# El-Fueradoro_Zuendbox.net
KiCad netlist of a schematic drawn in EAGLE
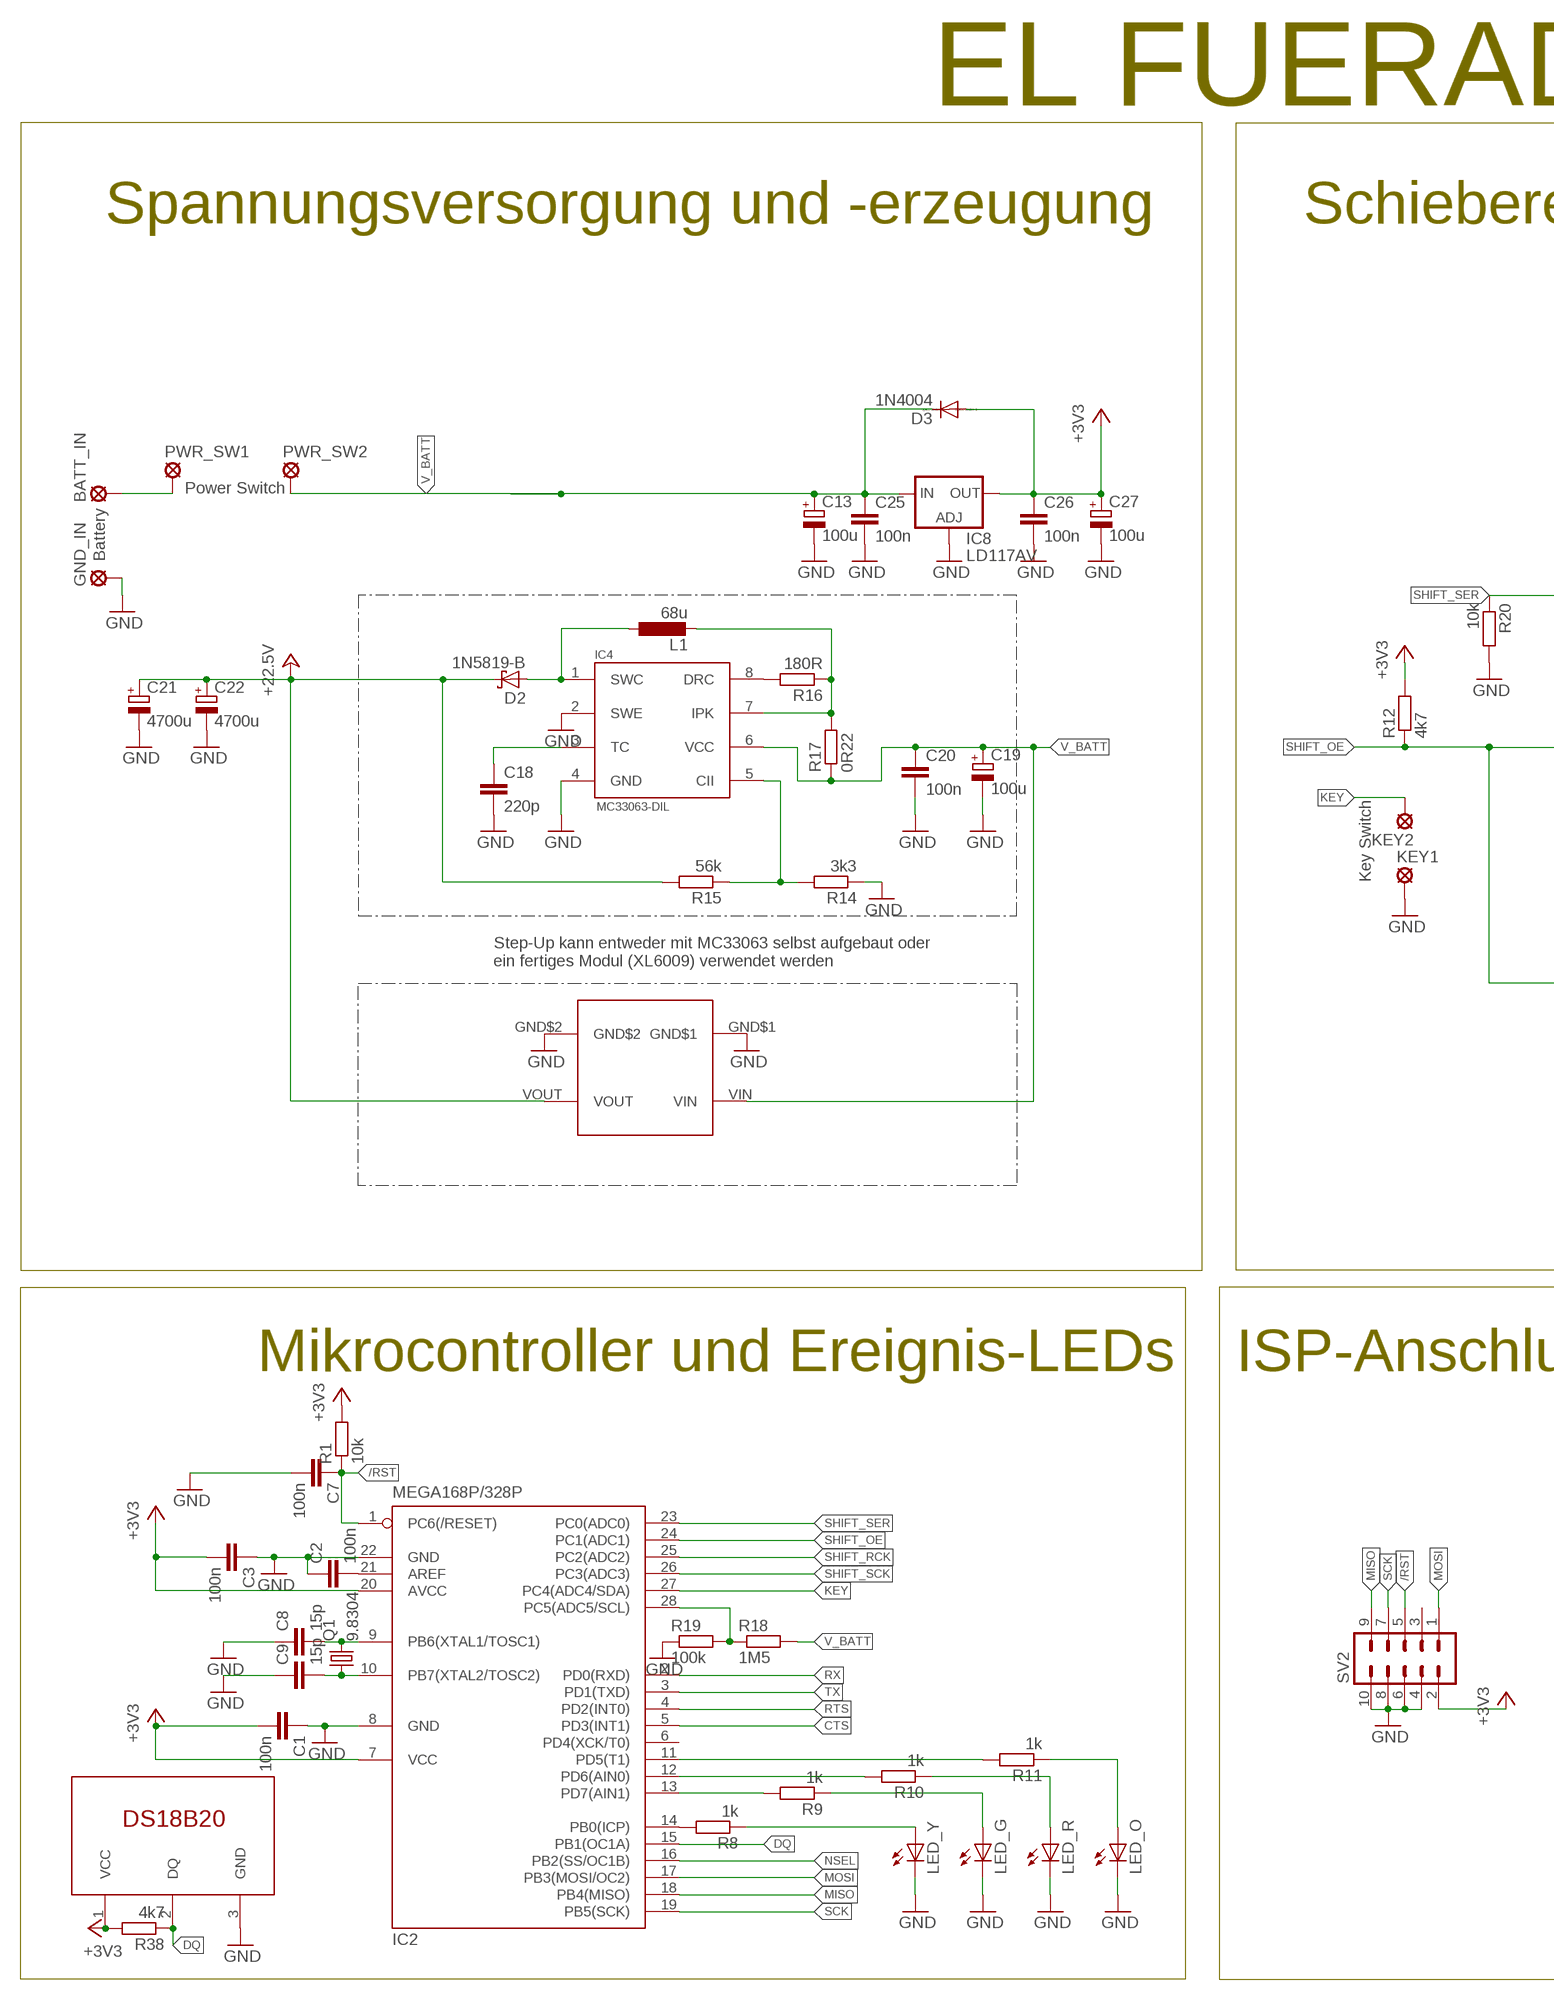
[diagram p0: schematic, sheet 1, part 1 of 2]
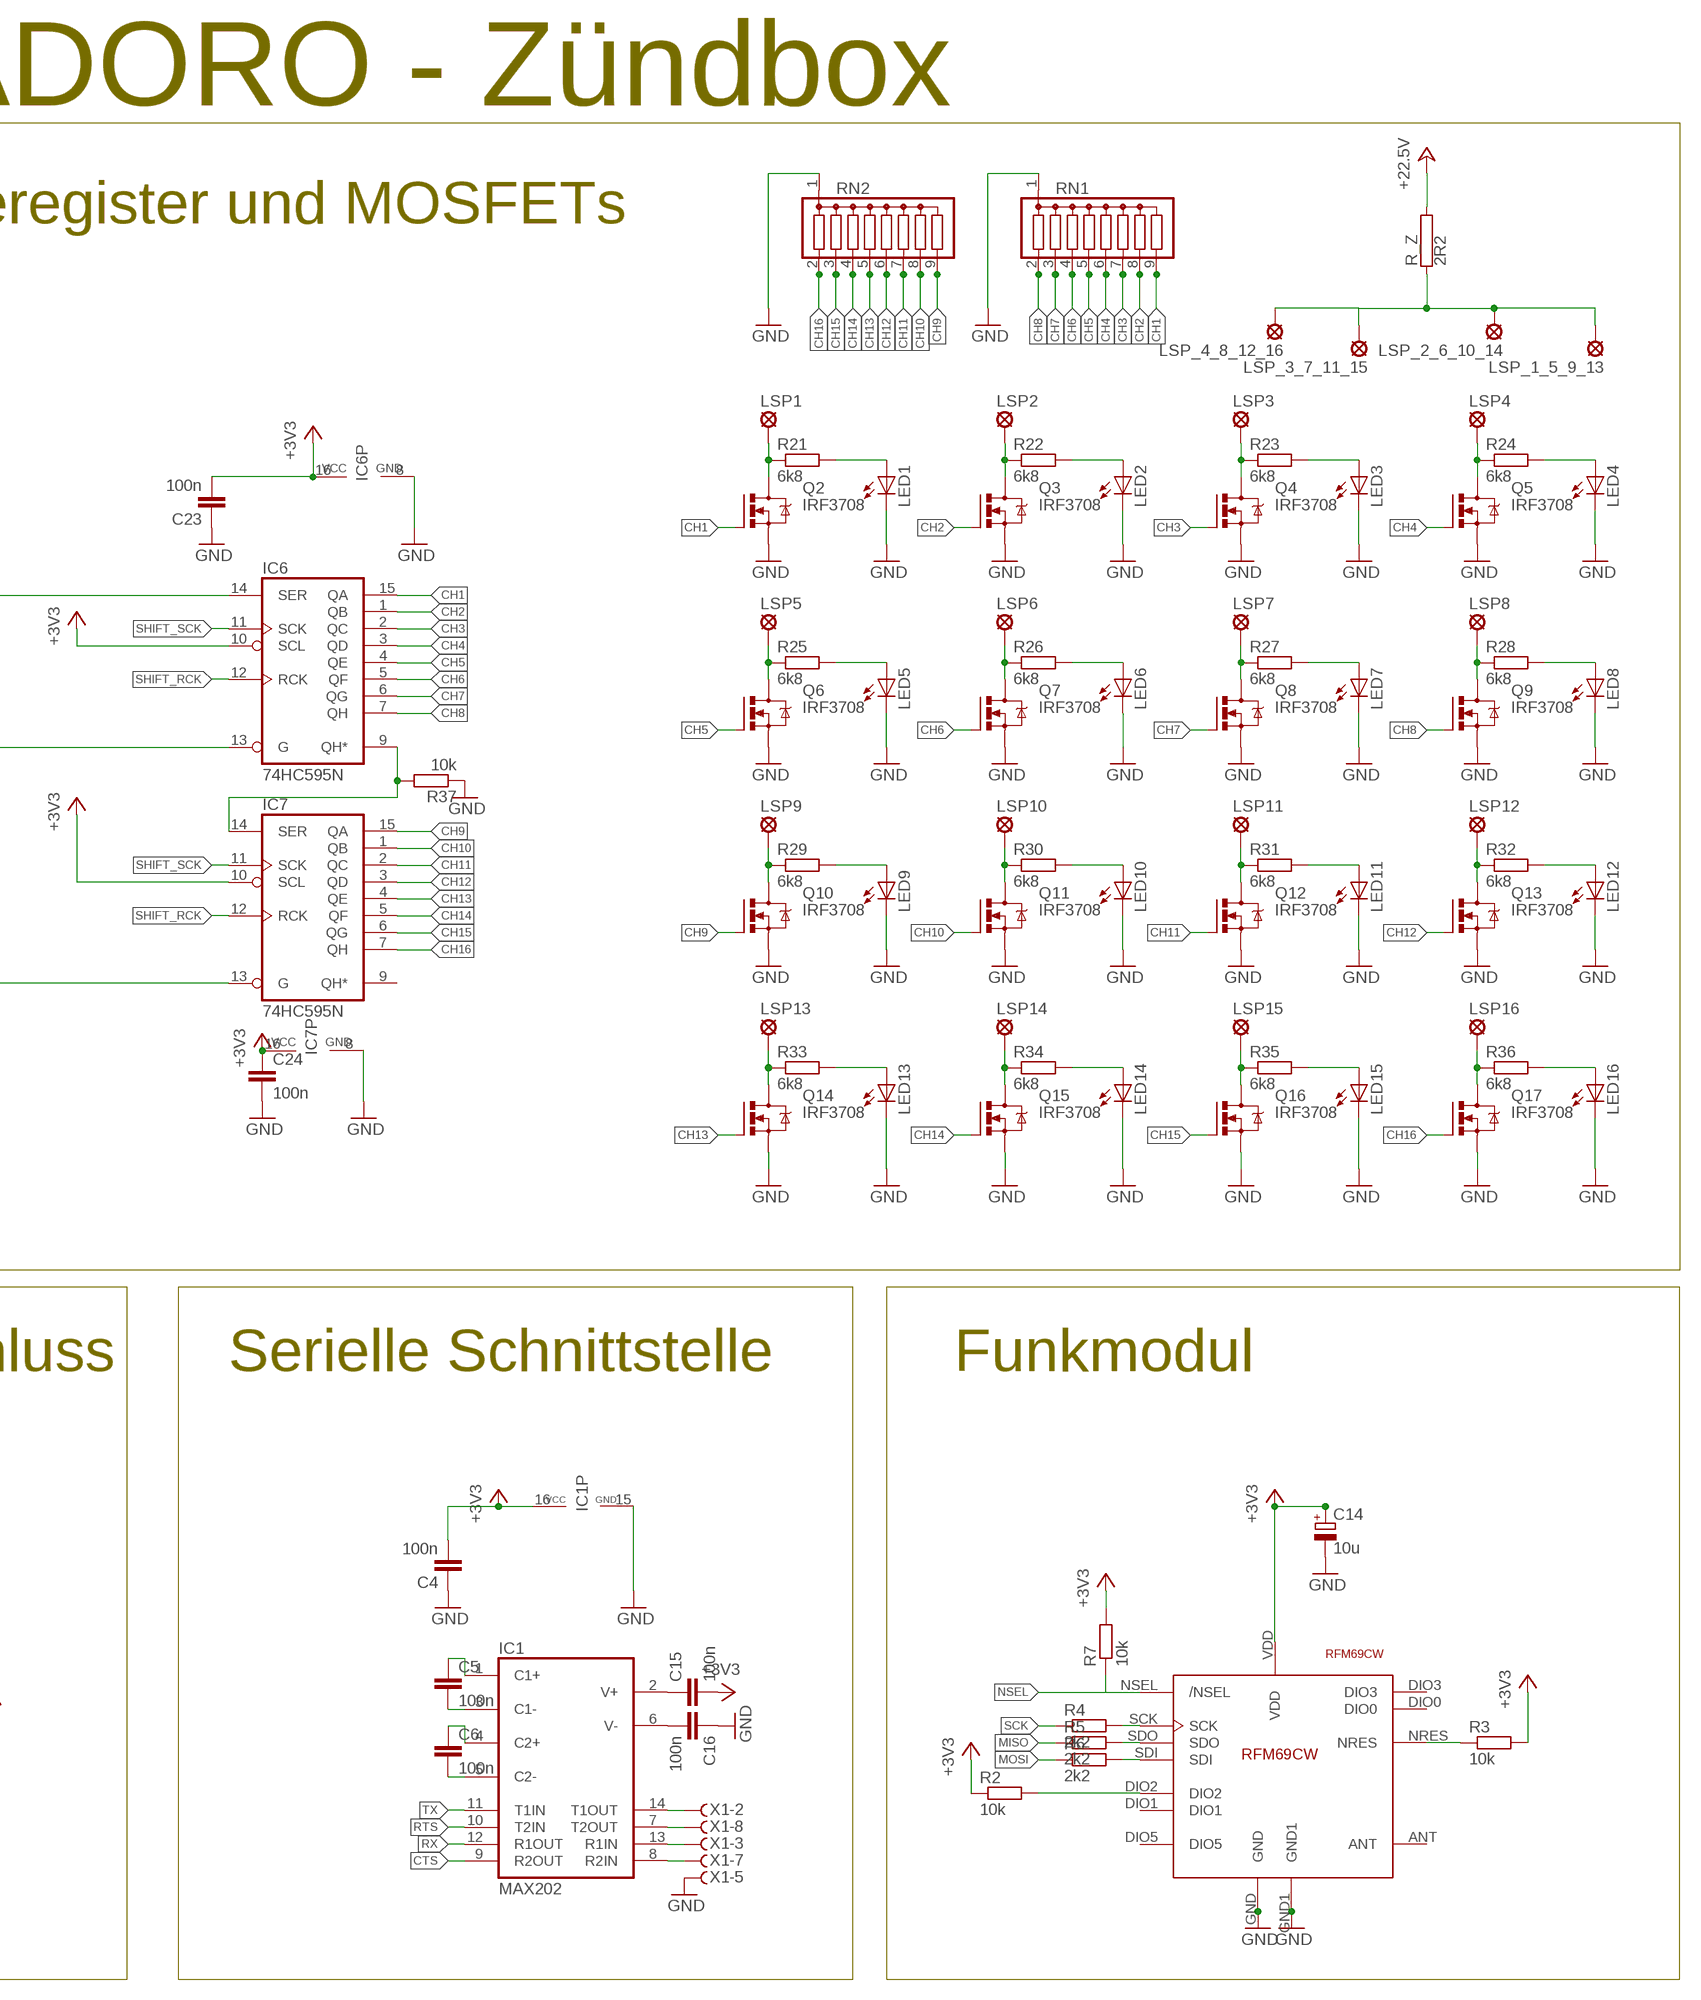
[diagram p1: schematic, sheet 1, part 2 of 2]

(export (version "E")
  (design (tool "Eeschema 10.0.6"))
  (components
    (comp (ref "BATT_IN")
      (value "LSP10")
      (footprint "eagle-import:LSP10")
      (libsource (lib "eagle-import") (part "LSP10"))
    )
    (comp (ref "C1")
      (value "100n")
      (footprint "eagle-import:C025-024X044")
      (libsource (lib "eagle-import") (part "C-EU025-024X044"))
    )
    (comp (ref "C2")
      (value "100n")
      (footprint "eagle-import:C025-024X044")
      (libsource (lib "eagle-import") (part "C-EU025-024X044"))
    )
    (comp (ref "C3")
      (value "100n")
      (footprint "eagle-import:C025-024X044")
      (libsource (lib "eagle-import") (part "C-EU025-024X044"))
    )
    (comp (ref "C4")
      (value "100n")
      (footprint "eagle-import:C025-024X044")
      (libsource (lib "eagle-import") (part "C-EU025-024X044"))
    )
    (comp (ref "C5")
      (value "100n")
      (footprint "eagle-import:C025-024X044")
      (libsource (lib "eagle-import") (part "C-EU025-024X044"))
    )
    (comp (ref "C6")
      (value "100n")
      (footprint "eagle-import:C025-024X044")
      (libsource (lib "eagle-import") (part "C-EU025-024X044"))
    )
    (comp (ref "C7")
      (value "100n")
      (footprint "eagle-import:C025-024X044")
      (libsource (lib "eagle-import") (part "C-EU025-024X044"))
    )
    (comp (ref "C8")
      (value "15p")
      (footprint "eagle-import:C025-024X044")
      (libsource (lib "eagle-import") (part "C-EU025-024X044"))
    )
    (comp (ref "C9")
      (value "15p")
      (footprint "eagle-import:C025-024X044")
      (libsource (lib "eagle-import") (part "C-EU025-024X044"))
    )
    (comp (ref "C13")
      (value "100u")
      (footprint "eagle-import:B45181A")
      (libsource (lib "eagle-import") (part "CPOL-EUB45181A"))
    )
    (comp (ref "C14")
      (value "10u")
      (footprint "eagle-import:B45181A")
      (libsource (lib "eagle-import") (part "CPOL-EUB45181A"))
    )
    (comp (ref "C15")
      (value "100n")
      (footprint "eagle-import:C025-024X044")
      (libsource (lib "eagle-import") (part "C-EU025-024X044"))
    )
    (comp (ref "C16")
      (value "100n")
      (footprint "eagle-import:C025-024X044")
      (libsource (lib "eagle-import") (part "C-EU025-024X044"))
    )
    (comp (ref "C18")
      (value "220p")
      (footprint "eagle-import:C025-024X044")
      (libsource (lib "eagle-import") (part "C-EU025-024X044"))
    )
    (comp (ref "C19")
      (value "100u")
      (footprint "eagle-import:E2,5-6E")
      (libsource (lib "eagle-import") (part "CPOL-EUE2,5-6E"))
    )
    (comp (ref "C20")
      (value "100n")
      (footprint "eagle-import:C025-024X044")
      (libsource (lib "eagle-import") (part "C-EU025-024X044"))
    )
    (comp (ref "C21")
      (value "4700u")
      (footprint "eagle-import:E7,5-18")
      (libsource (lib "eagle-import") (part "CPOL-EUE7.5-18"))
    )
    (comp (ref "C22")
      (value "4700u")
      (footprint "eagle-import:E7,5-18")
      (libsource (lib "eagle-import") (part "CPOL-EUE7.5-18"))
    )
    (comp (ref "C23")
      (value "100n")
      (footprint "eagle-import:C025-024X044")
      (libsource (lib "eagle-import") (part "C-EU025-024X044"))
    )
    (comp (ref "C24")
      (value "100n")
      (footprint "eagle-import:C025-024X044")
      (libsource (lib "eagle-import") (part "C-EU025-024X044"))
    )
    (comp (ref "C25")
      (value "100n")
      (footprint "eagle-import:C025-024X044")
      (libsource (lib "eagle-import") (part "C-EU025-024X044"))
    )
    (comp (ref "C26")
      (value "100n")
      (footprint "eagle-import:C025-024X044")
      (libsource (lib "eagle-import") (part "C-EU025-024X044"))
    )
    (comp (ref "C27")
      (value "100u")
      (footprint "eagle-import:B45181A")
      (libsource (lib "eagle-import") (part "CPOL-EUB45181A"))
    )
    (comp (ref "D2")
      (value "1N5819-B")
      (footprint "eagle-import:DO41-7.6")
      (libsource (lib "eagle-import") (part "1N5819-B"))
    )
    (comp (ref "D3")
      (value "1N4004")
      (footprint "eagle-import:DO41-10")
      (libsource (lib "eagle-import") (part "1N4004"))
    )
    (comp (ref "GND_IN")
      (value "LSP10")
      (footprint "eagle-import:LSP10")
      (libsource (lib "eagle-import") (part "LSP10"))
    )
    (comp (ref "IC1")
      (value "MAX202")
      (footprint "eagle-import:DIL16")
      (fields (field (name "MF") "MAXIM") (field (name "MPN") "MAX232ACPE+"))
      (libsource (lib "eagle-import") (part "MAX232"))
    )
    (comp (ref "IC2")
      (value "MEGA168P/328P")
      (footprint "eagle-import:DIL28-3")
      (libsource (lib "eagle-import") (part "MEGA8-P"))
    )
    (comp (ref "IC4")
      (value "MC33063-DIL")
      (footprint "eagle-import:DIL08")
      (libsource (lib "eagle-import") (part "MC34063-DIL"))
    )
    (comp (ref "IC6")
      (value "74HC595N")
      (footprint "eagle-import:DIL16")
      (libsource (lib "eagle-import") (part "74595NHC"))
    )
    (comp (ref "IC7")
      (value "74HC595N")
      (footprint "eagle-import:DIL16")
      (libsource (lib "eagle-import") (part "74595NHC"))
    )
    (comp (ref "IC8")
      (value "LD117AV")
      (footprint "eagle-import:TO220L1")
      (libsource (lib "eagle-import") (part "LD117A?V"))
    )
    (comp (ref "KEY1")
      (value "LSP10")
      (footprint "eagle-import:LSP10")
      (libsource (lib "eagle-import") (part "LSP10"))
    )
    (comp (ref "KEY2")
      (value "LSP10")
      (footprint "eagle-import:LSP10")
      (libsource (lib "eagle-import") (part "LSP10"))
    )
    (comp (ref "L1")
      (value "68u")
      (footprint "eagle-import:0204_5")
      (libsource (lib "eagle-import") (part "L-EU0204/5"))
    )
    (comp (ref "LED1")
      (value "LED3MM")
      (footprint "eagle-import:LED3MM")
      (libsource (lib "eagle-import") (part "LED3MM"))
    )
    (comp (ref "LED2")
      (value "LED3MM")
      (footprint "eagle-import:LED3MM")
      (libsource (lib "eagle-import") (part "LED3MM"))
    )
    (comp (ref "LED3")
      (value "LED3MM")
      (footprint "eagle-import:LED3MM")
      (libsource (lib "eagle-import") (part "LED3MM"))
    )
    (comp (ref "LED4")
      (value "LED3MM")
      (footprint "eagle-import:LED3MM")
      (libsource (lib "eagle-import") (part "LED3MM"))
    )
    (comp (ref "LED5")
      (value "LED3MM")
      (footprint "eagle-import:LED3MM")
      (libsource (lib "eagle-import") (part "LED3MM"))
    )
    (comp (ref "LED6")
      (value "LED3MM")
      (footprint "eagle-import:LED3MM")
      (libsource (lib "eagle-import") (part "LED3MM"))
    )
    (comp (ref "LED7")
      (value "LED3MM")
      (footprint "eagle-import:LED3MM")
      (libsource (lib "eagle-import") (part "LED3MM"))
    )
    (comp (ref "LED8")
      (value "LED3MM")
      (footprint "eagle-import:LED3MM")
      (libsource (lib "eagle-import") (part "LED3MM"))
    )
    (comp (ref "LED9")
      (value "LED3MM")
      (footprint "eagle-import:LED3MM")
      (libsource (lib "eagle-import") (part "LED3MM"))
    )
    (comp (ref "LED10")
      (value "LED3MM")
      (footprint "eagle-import:LED3MM")
      (libsource (lib "eagle-import") (part "LED3MM"))
    )
    (comp (ref "LED11")
      (value "LED3MM")
      (footprint "eagle-import:LED3MM")
      (libsource (lib "eagle-import") (part "LED3MM"))
    )
    (comp (ref "LED12")
      (value "LED3MM")
      (footprint "eagle-import:LED3MM")
      (libsource (lib "eagle-import") (part "LED3MM"))
    )
    (comp (ref "LED13")
      (value "LED3MM")
      (footprint "eagle-import:LED3MM")
      (libsource (lib "eagle-import") (part "LED3MM"))
    )
    (comp (ref "LED14")
      (value "LED3MM")
      (footprint "eagle-import:LED3MM")
      (libsource (lib "eagle-import") (part "LED3MM"))
    )
    (comp (ref "LED15")
      (value "LED3MM")
      (footprint "eagle-import:LED3MM")
      (libsource (lib "eagle-import") (part "LED3MM"))
    )
    (comp (ref "LED16")
      (value "LED3MM")
      (footprint "eagle-import:LED3MM")
      (libsource (lib "eagle-import") (part "LED3MM"))
    )
    (comp (ref "LED_G")
      (value "LED5MM")
      (footprint "eagle-import:LED5MM")
      (libsource (lib "eagle-import") (part "LED5MM"))
    )
    (comp (ref "LED_O")
      (value "LED5MM")
      (footprint "eagle-import:LED5MM")
      (libsource (lib "eagle-import") (part "LED5MM"))
    )
    (comp (ref "LED_R")
      (value "LED5MM")
      (footprint "eagle-import:LED5MM")
      (libsource (lib "eagle-import") (part "LED5MM"))
    )
    (comp (ref "LED_Y")
      (value "LED5MM")
      (footprint "eagle-import:LED5MM")
      (libsource (lib "eagle-import") (part "LED5MM"))
    )
    (comp (ref "LSP1")
      (value "LSP11")
      (footprint "eagle-import:LSP11")
      (libsource (lib "eagle-import") (part "LSP11"))
    )
    (comp (ref "LSP2")
      (value "LSP11")
      (footprint "eagle-import:LSP11")
      (libsource (lib "eagle-import") (part "LSP11"))
    )
    (comp (ref "LSP3")
      (value "LSP11")
      (footprint "eagle-import:LSP11")
      (libsource (lib "eagle-import") (part "LSP11"))
    )
    (comp (ref "LSP4")
      (value "LSP11")
      (footprint "eagle-import:LSP11")
      (libsource (lib "eagle-import") (part "LSP11"))
    )
    (comp (ref "LSP5")
      (value "LSP11")
      (footprint "eagle-import:LSP11")
      (libsource (lib "eagle-import") (part "LSP11"))
    )
    (comp (ref "LSP6")
      (value "LSP11")
      (footprint "eagle-import:LSP11")
      (libsource (lib "eagle-import") (part "LSP11"))
    )
    (comp (ref "LSP7")
      (value "LSP11")
      (footprint "eagle-import:LSP11")
      (libsource (lib "eagle-import") (part "LSP11"))
    )
    (comp (ref "LSP8")
      (value "LSP11")
      (footprint "eagle-import:LSP11")
      (libsource (lib "eagle-import") (part "LSP11"))
    )
    (comp (ref "LSP9")
      (value "LSP11")
      (footprint "eagle-import:LSP11")
      (libsource (lib "eagle-import") (part "LSP11"))
    )
    (comp (ref "LSP10")
      (value "LSP11")
      (footprint "eagle-import:LSP11")
      (libsource (lib "eagle-import") (part "LSP11"))
    )
    (comp (ref "LSP11")
      (value "LSP11")
      (footprint "eagle-import:LSP11")
      (libsource (lib "eagle-import") (part "LSP11"))
    )
    (comp (ref "LSP12")
      (value "LSP11")
      (footprint "eagle-import:LSP11")
      (libsource (lib "eagle-import") (part "LSP11"))
    )
    (comp (ref "LSP13")
      (value "LSP11")
      (footprint "eagle-import:LSP11")
      (libsource (lib "eagle-import") (part "LSP11"))
    )
    (comp (ref "LSP14")
      (value "LSP11")
      (footprint "eagle-import:LSP11")
      (libsource (lib "eagle-import") (part "LSP11"))
    )
    (comp (ref "LSP15")
      (value "LSP11")
      (footprint "eagle-import:LSP11")
      (libsource (lib "eagle-import") (part "LSP11"))
    )
    (comp (ref "LSP16")
      (value "LSP11")
      (footprint "eagle-import:LSP11")
      (libsource (lib "eagle-import") (part "LSP11"))
    )
    (comp (ref "LSP_1_5_9_13")
      (value "LSP11")
      (footprint "eagle-import:LSP11")
      (libsource (lib "eagle-import") (part "LSP11"))
    )
    (comp (ref "LSP_2_6_10_14")
      (value "LSP11")
      (footprint "eagle-import:LSP11")
      (libsource (lib "eagle-import") (part "LSP11"))
    )
    (comp (ref "LSP_3_7_11_15")
      (value "LSP11")
      (footprint "eagle-import:LSP11")
      (libsource (lib "eagle-import") (part "LSP11"))
    )
    (comp (ref "LSP_4_8_12_16")
      (value "LSP11")
      (footprint "eagle-import:LSP11")
      (libsource (lib "eagle-import") (part "LSP11"))
    )
    (comp (ref "PWR_SW1")
      (value "LSP10")
      (footprint "eagle-import:LSP10")
      (libsource (lib "eagle-import") (part "LSP10"))
    )
    (comp (ref "PWR_SW2")
      (value "LSP10")
      (footprint "eagle-import:LSP10")
      (libsource (lib "eagle-import") (part "LSP10"))
    )
    (comp (ref "Q1")
      (value "9.8304")
      (footprint "eagle-import:HC49_S")
      (libsource (lib "eagle-import") (part "CRYSTALHC49S"))
    )
    (comp (ref "Q2")
      (value "IRF3708")
      (footprint "eagle-import:TO220BV")
      (libsource (lib "eagle-import") (part "IRF530"))
    )
    (comp (ref "Q3")
      (value "IRF3708")
      (footprint "eagle-import:TO220BV")
      (libsource (lib "eagle-import") (part "IRF530"))
    )
    (comp (ref "Q4")
      (value "IRF3708")
      (footprint "eagle-import:TO220BV")
      (libsource (lib "eagle-import") (part "IRF530"))
    )
    (comp (ref "Q5")
      (value "IRF3708")
      (footprint "eagle-import:TO220BV")
      (libsource (lib "eagle-import") (part "IRF530"))
    )
    (comp (ref "Q6")
      (value "IRF3708")
      (footprint "eagle-import:TO220BV")
      (libsource (lib "eagle-import") (part "IRF530"))
    )
    (comp (ref "Q7")
      (value "IRF3708")
      (footprint "eagle-import:TO220BV")
      (libsource (lib "eagle-import") (part "IRF530"))
    )
    (comp (ref "Q8")
      (value "IRF3708")
      (footprint "eagle-import:TO220BV")
      (libsource (lib "eagle-import") (part "IRF530"))
    )
    (comp (ref "Q9")
      (value "IRF3708")
      (footprint "eagle-import:TO220BV")
      (libsource (lib "eagle-import") (part "IRF530"))
    )
    (comp (ref "Q10")
      (value "IRF3708")
      (footprint "eagle-import:TO220BV")
      (libsource (lib "eagle-import") (part "IRF530"))
    )
    (comp (ref "Q11")
      (value "IRF3708")
      (footprint "eagle-import:TO220BV")
      (libsource (lib "eagle-import") (part "IRF530"))
    )
    (comp (ref "Q12")
      (value "IRF3708")
      (footprint "eagle-import:TO220BV")
      (libsource (lib "eagle-import") (part "IRF530"))
    )
    (comp (ref "Q13")
      (value "IRF3708")
      (footprint "eagle-import:TO220BV")
      (libsource (lib "eagle-import") (part "IRF530"))
    )
    (comp (ref "Q14")
      (value "IRF3708")
      (footprint "eagle-import:TO220BV")
      (libsource (lib "eagle-import") (part "IRF530"))
    )
    (comp (ref "Q15")
      (value "IRF3708")
      (footprint "eagle-import:TO220BV")
      (libsource (lib "eagle-import") (part "IRF530"))
    )
    (comp (ref "Q16")
      (value "IRF3708")
      (footprint "eagle-import:TO220BV")
      (libsource (lib "eagle-import") (part "IRF530"))
    )
    (comp (ref "Q17")
      (value "IRF3708")
      (footprint "eagle-import:TO220BV")
      (libsource (lib "eagle-import") (part "IRF530"))
    )
    (comp (ref "R1")
      (value "10k")
      (footprint "eagle-import:0207_10")
      (libsource (lib "eagle-import") (part "R-EU_0207/10"))
    )
    (comp (ref "R2")
      (value "10k")
      (footprint "eagle-import:0207_10")
      (libsource (lib "eagle-import") (part "R-EU_0207/10"))
    )
    (comp (ref "R3")
      (value "10k")
      (footprint "eagle-import:0207_10")
      (libsource (lib "eagle-import") (part "R-EU_0207/10"))
    )
    (comp (ref "R4")
      (value "2k2")
      (footprint "eagle-import:0207_10")
      (libsource (lib "eagle-import") (part "R-EU_0207/10"))
    )
    (comp (ref "R5")
      (value "2k2")
      (footprint "eagle-import:0207_10")
      (libsource (lib "eagle-import") (part "R-EU_0207/10"))
    )
    (comp (ref "R6")
      (value "2k2")
      (footprint "eagle-import:0207_10")
      (libsource (lib "eagle-import") (part "R-EU_0207/10"))
    )
    (comp (ref "R7")
      (value "10k")
      (footprint "eagle-import:0207_10")
      (libsource (lib "eagle-import") (part "R-EU_0207/10"))
    )
    (comp (ref "R8")
      (value "1k")
      (footprint "eagle-import:0207_10")
      (libsource (lib "eagle-import") (part "R-EU_0207/10"))
    )
    (comp (ref "R9")
      (value "1k")
      (footprint "eagle-import:0207_10")
      (libsource (lib "eagle-import") (part "R-EU_0207/10"))
    )
    (comp (ref "R10")
      (value "1k")
      (footprint "eagle-import:0207_10")
      (libsource (lib "eagle-import") (part "R-EU_0207/10"))
    )
    (comp (ref "R11")
      (value "1k")
      (footprint "eagle-import:0207_10")
      (libsource (lib "eagle-import") (part "R-EU_0207/10"))
    )
    (comp (ref "R12")
      (value "4k7")
      (footprint "eagle-import:0207_10")
      (libsource (lib "eagle-import") (part "R-EU_0207/10"))
    )
    (comp (ref "R14")
      (value "3k3")
      (footprint "eagle-import:0207_10")
      (libsource (lib "eagle-import") (part "R-EU_0207/10"))
    )
    (comp (ref "R15")
      (value "56k")
      (footprint "eagle-import:0207_10")
      (libsource (lib "eagle-import") (part "R-EU_0207/10"))
    )
    (comp (ref "R16")
      (value "180R")
      (footprint "eagle-import:0207_10")
      (libsource (lib "eagle-import") (part "R-EU_0207/10"))
    )
    (comp (ref "R17")
      (value "0R22")
      (footprint "eagle-import:0207_10")
      (libsource (lib "eagle-import") (part "R-EU_0207/10"))
    )
    (comp (ref "R18")
      (value "1M5")
      (footprint "eagle-import:0207_10")
      (libsource (lib "eagle-import") (part "R-EU_0207/10"))
    )
    (comp (ref "R19")
      (value "100k")
      (footprint "eagle-import:0207_10")
      (libsource (lib "eagle-import") (part "R-EU_0207/10"))
    )
    (comp (ref "R20")
      (value "10k")
      (footprint "eagle-import:0207_10")
      (libsource (lib "eagle-import") (part "R-EU_0207/10"))
    )
    (comp (ref "R21")
      (value "6k8")
      (footprint "eagle-import:0207_10")
      (libsource (lib "eagle-import") (part "R-EU_0207/10"))
    )
    (comp (ref "R22")
      (value "6k8")
      (footprint "eagle-import:0207_10")
      (libsource (lib "eagle-import") (part "R-EU_0207/10"))
    )
    (comp (ref "R23")
      (value "6k8")
      (footprint "eagle-import:0207_10")
      (libsource (lib "eagle-import") (part "R-EU_0207/10"))
    )
    (comp (ref "R24")
      (value "6k8")
      (footprint "eagle-import:0207_10")
      (libsource (lib "eagle-import") (part "R-EU_0207/10"))
    )
    (comp (ref "R25")
      (value "6k8")
      (footprint "eagle-import:0207_10")
      (libsource (lib "eagle-import") (part "R-EU_0207/10"))
    )
    (comp (ref "R26")
      (value "6k8")
      (footprint "eagle-import:0207_10")
      (libsource (lib "eagle-import") (part "R-EU_0207/10"))
    )
    (comp (ref "R27")
      (value "6k8")
      (footprint "eagle-import:0207_10")
      (libsource (lib "eagle-import") (part "R-EU_0207/10"))
    )
    (comp (ref "R28")
      (value "6k8")
      (footprint "eagle-import:0207_10")
      (libsource (lib "eagle-import") (part "R-EU_0207/10"))
    )
    (comp (ref "R29")
      (value "6k8")
      (footprint "eagle-import:0207_10")
      (libsource (lib "eagle-import") (part "R-EU_0207/10"))
    )
    (comp (ref "R30")
      (value "6k8")
      (footprint "eagle-import:0207_10")
      (libsource (lib "eagle-import") (part "R-EU_0207/10"))
    )
    (comp (ref "R31")
      (value "6k8")
      (footprint "eagle-import:0207_10")
      (libsource (lib "eagle-import") (part "R-EU_0207/10"))
    )
    (comp (ref "R32")
      (value "6k8")
      (footprint "eagle-import:0207_10")
      (libsource (lib "eagle-import") (part "R-EU_0207/10"))
    )
    (comp (ref "R33")
      (value "6k8")
      (footprint "eagle-import:0207_10")
      (libsource (lib "eagle-import") (part "R-EU_0207/10"))
    )
    (comp (ref "R34")
      (value "6k8")
      (footprint "eagle-import:0207_10")
      (libsource (lib "eagle-import") (part "R-EU_0207/10"))
    )
    (comp (ref "R35")
      (value "6k8")
      (footprint "eagle-import:0207_10")
      (libsource (lib "eagle-import") (part "R-EU_0207/10"))
    )
    (comp (ref "R36")
      (value "6k8")
      (footprint "eagle-import:0207_10")
      (libsource (lib "eagle-import") (part "R-EU_0207/10"))
    )
    (comp (ref "R37")
      (value "10k")
      (footprint "eagle-import:0207_10")
      (libsource (lib "eagle-import") (part "R-EU_0207/10"))
    )
    (comp (ref "R38")
      (value "4k7")
      (footprint "eagle-import:0207_10")
      (libsource (lib "eagle-import") (part "R-EU_0207/10"))
    )
    (comp (ref "RN1")
      (value "G08R")
      (footprint "eagle-import:SIL9")
      (libsource (lib "eagle-import") (part "G08R"))
    )
    (comp (ref "RN2")
      (value "G08R")
      (footprint "eagle-import:SIL9")
      (libsource (lib "eagle-import") (part "G08R"))
    )
    (comp (ref "R_Z")
      (value "2R2")
      (footprint "eagle-import:KH214R-8")
      (libsource (lib "eagle-import") (part "RKH214-8R"))
    )
    (comp (ref "SV2")
      (value "ML10")
      (footprint "eagle-import:ML10")
      (libsource (lib "eagle-import") (part "ML10"))
    )
    (comp (ref "U$2")
      (value "DS18B20")
      (footprint "eagle-import:TO92-LINE")
      (libsource (lib "eagle-import") (part "DS18B20"))
    )
    (comp (ref "U$3")
      (value "XL6009_MODULED")
      (footprint "eagle-import:XL6009_PACK")
      (libsource (lib "eagle-import") (part "XL6009_MODULED"))
    )
    (comp (ref "U$4")
      (value "RFM69CW")
      (footprint "eagle-import:RFM69CW")
      (libsource (lib "eagle-import") (part "RFM69CW"))
    )
    (comp (ref "X1")
      (value "F09HPS")
      (footprint "eagle-import:F09HP")
      (libsource (lib "eagle-import") (part "F09HPS"))
    )
  )
  (nets
    (net (code "1") (name "+3V3") (class "Default")
      (node (ref "C1") (pin "2") (pinfunction "2_2") (pintype "passive"))
      (node (ref "C14") (pin "+") (pinfunction "+_+") (pintype "passive"))
      (node (ref "C15") (pin "2") (pinfunction "2_2") (pintype "passive"))
      (node (ref "C23") (pin "2") (pinfunction "2_2") (pintype "passive"))
      (node (ref "C24") (pin "1") (pinfunction "1_1") (pintype "passive"))
      (node (ref "C26") (pin "1") (pinfunction "1_1") (pintype "passive"))
      (node (ref "C27") (pin "+") (pinfunction "+_+") (pintype "passive"))
      (node (ref "C3") (pin "2") (pinfunction "2_2") (pintype "passive"))
      (node (ref "C4") (pin "2") (pinfunction "2_2") (pintype "passive"))
      (node (ref "D3") (pin "A") (pinfunction "A_A") (pintype "passive"))
      (node (ref "IC1") (pin "16") (pinfunction "VCC_16") (pintype "power_in"))
      (node (ref "IC2") (pin "20") (pinfunction "AVCC_20") (pintype "power_in"))
      (node (ref "IC2") (pin "7") (pinfunction "VCC_7") (pintype "power_in"))
      (node (ref "IC6") (pin "10") (pinfunction "SCL_10") (pintype "input"))
      (node (ref "IC6") (pin "16") (pinfunction "VCC_16") (pintype "power_in"))
      (node (ref "IC7") (pin "10") (pinfunction "SCL_10") (pintype "input"))
      (node (ref "IC7") (pin "16") (pinfunction "VCC_16") (pintype "power_in"))
      (node (ref "IC8") (pin "2") (pinfunction "OUT_2") (pintype "passive"))
      (node (ref "R1") (pin "2") (pinfunction "2_2") (pintype "passive"))
      (node (ref "R12") (pin "2") (pinfunction "2_2") (pintype "passive"))
      (node (ref "R2") (pin "1") (pinfunction "1_1") (pintype "passive"))
      (node (ref "R3") (pin "2") (pinfunction "2_2") (pintype "passive"))
      (node (ref "R38") (pin "2") (pinfunction "2_2") (pintype "passive"))
      (node (ref "R7") (pin "2") (pinfunction "2_2") (pintype "passive"))
      (node (ref "SV2") (pin "2") (pinfunction "2_2") (pintype "passive"))
      (node (ref "U$2") (pin "1") (pinfunction "VCC_1") (pintype "power_in"))
      (node (ref "U$4") (pin "VDD") (pinfunction "VDD_VDD") (pintype "power_in"))
    )
    (net (code "2") (name "+22.5V") (class "Default")
      (node (ref "C21") (pin "+") (pinfunction "+_+") (pintype "passive"))
      (node (ref "C22") (pin "+") (pinfunction "+_+") (pintype "passive"))
      (node (ref "D2") (pin "C") (pinfunction "C_C") (pintype "passive"))
      (node (ref "R15") (pin "2") (pinfunction "2_2") (pintype "passive"))
      (node (ref "R_Z") (pin "2") (pinfunction "2_2") (pintype "passive"))
      (node (ref "U$3") (pin "VOUT") (pinfunction "VOUT_VOUT") (pintype "bidirectional"))
    )
    (net (code "3") (name "CH1") (class "Default")
      (node (ref "IC6") (pin "15") (pinfunction "QA_15") (pintype "tri_state"))
      (node (ref "Q2") (pin "G") (pinfunction "G_G") (pintype "passive"))
      (node (ref "RN1") (pin "9") (pinfunction "9_9") (pintype "passive"))
    )
    (net (code "4") (name "CH2") (class "Default")
      (node (ref "IC6") (pin "1") (pinfunction "QB_1") (pintype "tri_state"))
      (node (ref "Q3") (pin "G") (pinfunction "G_G") (pintype "passive"))
      (node (ref "RN1") (pin "8") (pinfunction "8_8") (pintype "passive"))
    )
    (net (code "5") (name "CH3") (class "Default")
      (node (ref "IC6") (pin "2") (pinfunction "QC_2") (pintype "tri_state"))
      (node (ref "Q4") (pin "G") (pinfunction "G_G") (pintype "passive"))
      (node (ref "RN1") (pin "7") (pinfunction "7_7") (pintype "passive"))
    )
    (net (code "6") (name "CH4") (class "Default")
      (node (ref "IC6") (pin "3") (pinfunction "QD_3") (pintype "tri_state"))
      (node (ref "Q5") (pin "G") (pinfunction "G_G") (pintype "passive"))
      (node (ref "RN1") (pin "6") (pinfunction "6_6") (pintype "passive"))
    )
    (net (code "7") (name "CH5") (class "Default")
      (node (ref "IC6") (pin "4") (pinfunction "QE_4") (pintype "tri_state"))
      (node (ref "Q6") (pin "G") (pinfunction "G_G") (pintype "passive"))
      (node (ref "RN1") (pin "5") (pinfunction "5_5") (pintype "passive"))
    )
    (net (code "8") (name "CH6") (class "Default")
      (node (ref "IC6") (pin "5") (pinfunction "QF_5") (pintype "tri_state"))
      (node (ref "Q7") (pin "G") (pinfunction "G_G") (pintype "passive"))
      (node (ref "RN1") (pin "4") (pinfunction "4_4") (pintype "passive"))
    )
    (net (code "9") (name "CH7") (class "Default")
      (node (ref "IC6") (pin "6") (pinfunction "QG_6") (pintype "tri_state"))
      (node (ref "Q8") (pin "G") (pinfunction "G_G") (pintype "passive"))
      (node (ref "RN1") (pin "3") (pinfunction "3_3") (pintype "passive"))
    )
    (net (code "10") (name "CH8") (class "Default")
      (node (ref "IC6") (pin "7") (pinfunction "QH_7") (pintype "tri_state"))
      (node (ref "Q9") (pin "G") (pinfunction "G_G") (pintype "passive"))
      (node (ref "RN1") (pin "2") (pinfunction "2_2") (pintype "passive"))
    )
    (net (code "11") (name "CH9") (class "Default")
      (node (ref "IC7") (pin "15") (pinfunction "QA_15") (pintype "tri_state"))
      (node (ref "Q10") (pin "G") (pinfunction "G_G") (pintype "passive"))
      (node (ref "RN2") (pin "9") (pinfunction "9_9") (pintype "passive"))
    )
    (net (code "12") (name "CH10") (class "Default")
      (node (ref "IC7") (pin "1") (pinfunction "QB_1") (pintype "tri_state"))
      (node (ref "Q11") (pin "G") (pinfunction "G_G") (pintype "passive"))
      (node (ref "RN2") (pin "8") (pinfunction "8_8") (pintype "passive"))
    )
    (net (code "13") (name "CH11") (class "Default")
      (node (ref "IC7") (pin "2") (pinfunction "QC_2") (pintype "tri_state"))
      (node (ref "Q12") (pin "G") (pinfunction "G_G") (pintype "passive"))
      (node (ref "RN2") (pin "7") (pinfunction "7_7") (pintype "passive"))
    )
    (net (code "14") (name "CH12") (class "Default")
      (node (ref "IC7") (pin "3") (pinfunction "QD_3") (pintype "tri_state"))
      (node (ref "Q13") (pin "G") (pinfunction "G_G") (pintype "passive"))
      (node (ref "RN2") (pin "6") (pinfunction "6_6") (pintype "passive"))
    )
    (net (code "15") (name "CH13") (class "Default")
      (node (ref "IC7") (pin "4") (pinfunction "QE_4") (pintype "tri_state"))
      (node (ref "Q14") (pin "G") (pinfunction "G_G") (pintype "passive"))
      (node (ref "RN2") (pin "5") (pinfunction "5_5") (pintype "passive"))
    )
    (net (code "16") (name "CH14") (class "Default")
      (node (ref "IC7") (pin "5") (pinfunction "QF_5") (pintype "tri_state"))
      (node (ref "Q15") (pin "G") (pinfunction "G_G") (pintype "passive"))
      (node (ref "RN2") (pin "4") (pinfunction "4_4") (pintype "passive"))
    )
    (net (code "17") (name "CH15") (class "Default")
      (node (ref "IC7") (pin "6") (pinfunction "QG_6") (pintype "tri_state"))
      (node (ref "Q16") (pin "G") (pinfunction "G_G") (pintype "passive"))
      (node (ref "RN2") (pin "3") (pinfunction "3_3") (pintype "passive"))
    )
    (net (code "18") (name "CH16") (class "Default")
      (node (ref "IC7") (pin "7") (pinfunction "QH_7") (pintype "tri_state"))
      (node (ref "Q17") (pin "G") (pinfunction "G_G") (pintype "passive"))
      (node (ref "RN2") (pin "2") (pinfunction "2_2") (pintype "passive"))
    )
    (net (code "19") (name "CTS") (class "Default")
      (node (ref "IC1") (pin "9") (pinfunction "R2OUT_9") (pintype "output"))
      (node (ref "IC2") (pin "5") (pinfunction "PD3(INT1)_5") (pintype "bidirectional"))
    )
    (net (code "20") (name "DQ") (class "Default")
      (node (ref "IC2") (pin "15") (pinfunction "PB1(OC1A)_15") (pintype "bidirectional"))
      (node (ref "R38") (pin "1") (pinfunction "1_1") (pintype "passive"))
      (node (ref "U$2") (pin "2") (pinfunction "DQ_2") (pintype "bidirectional"))
    )
    (net (code "21") (name "GND") (class "Default")
      (node (ref "C1") (pin "1") (pinfunction "1_1") (pintype "passive"))
      (node (ref "C13") (pin "-") (pinfunction "-_-") (pintype "passive"))
      (node (ref "C14") (pin "-") (pinfunction "-_-") (pintype "passive"))
      (node (ref "C16") (pin "1") (pinfunction "1_1") (pintype "passive"))
      (node (ref "C18") (pin "2") (pinfunction "2_2") (pintype "passive"))
      (node (ref "C19") (pin "-") (pinfunction "-_-") (pintype "passive"))
      (node (ref "C2") (pin "1") (pinfunction "1_1") (pintype "passive"))
      (node (ref "C20") (pin "2") (pinfunction "2_2") (pintype "passive"))
      (node (ref "C21") (pin "-") (pinfunction "-_-") (pintype "passive"))
      (node (ref "C22") (pin "-") (pinfunction "-_-") (pintype "passive"))
      (node (ref "C23") (pin "1") (pinfunction "1_1") (pintype "passive"))
      (node (ref "C24") (pin "2") (pinfunction "2_2") (pintype "passive"))
      (node (ref "C25") (pin "2") (pinfunction "2_2") (pintype "passive"))
      (node (ref "C26") (pin "2") (pinfunction "2_2") (pintype "passive"))
      (node (ref "C27") (pin "-") (pinfunction "-_-") (pintype "passive"))
      (node (ref "C3") (pin "1") (pinfunction "1_1") (pintype "passive"))
      (node (ref "C4") (pin "1") (pinfunction "1_1") (pintype "passive"))
      (node (ref "C7") (pin "2") (pinfunction "2_2") (pintype "passive"))
      (node (ref "C8") (pin "1") (pinfunction "1_1") (pintype "passive"))
      (node (ref "C9") (pin "1") (pinfunction "1_1") (pintype "passive"))
      (node (ref "GND_IN") (pin "MP") (pinfunction "MP_MP") (pintype "passive"))
      (node (ref "IC1") (pin "15") (pinfunction "GND_15") (pintype "power_in"))
      (node (ref "IC2") (pin "22") (pinfunction "GND_22") (pintype "power_in"))
      (node (ref "IC2") (pin "8") (pinfunction "GND_8") (pintype "power_in"))
      (node (ref "IC4") (pin "2") (pinfunction "SWE_2") (pintype "bidirectional"))
      (node (ref "IC4") (pin "4") (pinfunction "GND_4") (pintype "power_in"))
      (node (ref "IC6") (pin "8") (pinfunction "GND_8") (pintype "power_in"))
      (node (ref "IC7") (pin "8") (pinfunction "GND_8") (pintype "power_in"))
      (node (ref "IC8") (pin "1") (pinfunction "ADJ_1") (pintype "input"))
      (node (ref "KEY1") (pin "MP") (pinfunction "MP_MP") (pintype "passive"))
      (node (ref "LED1") (pin "K") (pinfunction "C_K") (pintype "passive"))
      (node (ref "LED10") (pin "K") (pinfunction "C_K") (pintype "passive"))
      (node (ref "LED11") (pin "K") (pinfunction "C_K") (pintype "passive"))
      (node (ref "LED12") (pin "K") (pinfunction "C_K") (pintype "passive"))
      (node (ref "LED13") (pin "K") (pinfunction "C_K") (pintype "passive"))
      (node (ref "LED14") (pin "K") (pinfunction "C_K") (pintype "passive"))
      (node (ref "LED15") (pin "K") (pinfunction "C_K") (pintype "passive"))
      (node (ref "LED16") (pin "K") (pinfunction "C_K") (pintype "passive"))
      (node (ref "LED2") (pin "K") (pinfunction "C_K") (pintype "passive"))
      (node (ref "LED3") (pin "K") (pinfunction "C_K") (pintype "passive"))
      (node (ref "LED4") (pin "K") (pinfunction "C_K") (pintype "passive"))
      (node (ref "LED5") (pin "K") (pinfunction "C_K") (pintype "passive"))
      (node (ref "LED6") (pin "K") (pinfunction "C_K") (pintype "passive"))
      (node (ref "LED7") (pin "K") (pinfunction "C_K") (pintype "passive"))
      (node (ref "LED8") (pin "K") (pinfunction "C_K") (pintype "passive"))
      (node (ref "LED9") (pin "K") (pinfunction "C_K") (pintype "passive"))
      (node (ref "LED_G") (pin "K") (pinfunction "C_K") (pintype "passive"))
      (node (ref "LED_O") (pin "K") (pinfunction "C_K") (pintype "passive"))
      (node (ref "LED_R") (pin "K") (pinfunction "C_K") (pintype "passive"))
      (node (ref "LED_Y") (pin "K") (pinfunction "C_K") (pintype "passive"))
      (node (ref "Q10") (pin "S") (pinfunction "S_S") (pintype "passive"))
      (node (ref "Q11") (pin "S") (pinfunction "S_S") (pintype "passive"))
      (node (ref "Q12") (pin "S") (pinfunction "S_S") (pintype "passive"))
      (node (ref "Q13") (pin "S") (pinfunction "S_S") (pintype "passive"))
      (node (ref "Q14") (pin "S") (pinfunction "S_S") (pintype "passive"))
      (node (ref "Q15") (pin "S") (pinfunction "S_S") (pintype "passive"))
      (node (ref "Q16") (pin "S") (pinfunction "S_S") (pintype "passive"))
      (node (ref "Q17") (pin "S") (pinfunction "S_S") (pintype "passive"))
      (node (ref "Q2") (pin "S") (pinfunction "S_S") (pintype "passive"))
      (node (ref "Q3") (pin "S") (pinfunction "S_S") (pintype "passive"))
      (node (ref "Q4") (pin "S") (pinfunction "S_S") (pintype "passive"))
      (node (ref "Q5") (pin "S") (pinfunction "S_S") (pintype "passive"))
      (node (ref "Q6") (pin "S") (pinfunction "S_S") (pintype "passive"))
      (node (ref "Q7") (pin "S") (pinfunction "S_S") (pintype "passive"))
      (node (ref "Q8") (pin "S") (pinfunction "S_S") (pintype "passive"))
      (node (ref "Q9") (pin "S") (pinfunction "S_S") (pintype "passive"))
      (node (ref "R14") (pin "1") (pinfunction "1_1") (pintype "passive"))
      (node (ref "R19") (pin "1") (pinfunction "1_1") (pintype "passive"))
      (node (ref "R20") (pin "2") (pinfunction "2_2") (pintype "passive"))
      (node (ref "R37") (pin "1") (pinfunction "1_1") (pintype "passive"))
      (node (ref "RN1") (pin "1") (pinfunction "1_1") (pintype "passive"))
      (node (ref "RN2") (pin "1") (pinfunction "1_1") (pintype "passive"))
      (node (ref "SV2") (pin "10") (pinfunction "10_10") (pintype "passive"))
      (node (ref "SV2") (pin "4") (pinfunction "4_4") (pintype "passive"))
      (node (ref "SV2") (pin "6") (pinfunction "6_6") (pintype "passive"))
      (node (ref "SV2") (pin "8") (pinfunction "8_8") (pintype "passive"))
      (node (ref "U$2") (pin "3") (pinfunction "GND_3") (pintype "power_in"))
      (node (ref "U$3") (pin "GND$1") (pinfunction "GND$1_GND$1") (pintype "bidirectional"))
      (node (ref "U$3") (pin "GND$2") (pinfunction "GND$2_GND$2") (pintype "bidirectional"))
      (node (ref "U$4") (pin "GND") (pinfunction "GND_GND") (pintype "power_in"))
      (node (ref "U$4") (pin "GND1") (pinfunction "GND1_GND1") (pintype "power_in"))
      (node (ref "X1") (pin "5") (pinfunction "F_5") (pintype "passive"))
    )
    (net (code "22") (name "KEY") (class "Default")
      (node (ref "IC2") (pin "27") (pinfunction "PC4(ADC4/SDA)_27") (pintype "bidirectional"))
      (node (ref "KEY2") (pin "MP") (pinfunction "MP_MP") (pintype "passive"))
    )
    (net (code "23") (name "MISO") (class "Default")
      (node (ref "IC2") (pin "18") (pinfunction "PB4(MISO)_18") (pintype "bidirectional"))
      (node (ref "R5") (pin "1") (pinfunction "1_1") (pintype "passive"))
      (node (ref "SV2") (pin "9") (pinfunction "9_9") (pintype "passive"))
    )
    (net (code "24") (name "MOSI") (class "Default")
      (node (ref "IC2") (pin "17") (pinfunction "PB3(MOSI/OC2)_17") (pintype "bidirectional"))
      (node (ref "R6") (pin "1") (pinfunction "1_1") (pintype "passive"))
      (node (ref "SV2") (pin "1") (pinfunction "1_1") (pintype "passive"))
    )
    (net (code "25") (name "NSEL") (class "Default")
      (node (ref "IC2") (pin "16") (pinfunction "PB2(SS/OC1B)_16") (pintype "bidirectional"))
      (node (ref "R7") (pin "1") (pinfunction "1_1") (pintype "passive"))
      (node (ref "U$4") (pin "NSEL") (pinfunction "/NSEL_NSEL") (pintype "input"))
    )
    (net (code "26") (name "Net-(BATT_IN-PadMP)") (class "Default")
      (node (ref "BATT_IN") (pin "MP") (pinfunction "MP_MP") (pintype "passive"))
      (node (ref "PWR_SW1") (pin "MP") (pinfunction "MP_MP") (pintype "passive"))
    )
    (net (code "27") (name "Net-(IC1A-C1+)") (class "Default")
      (node (ref "C5") (pin "1") (pinfunction "1_1") (pintype "passive"))
      (node (ref "IC1") (pin "1") (pinfunction "C1+_1") (pintype "bidirectional"))
    )
    (net (code "28") (name "Net-(IC1A-C1-)") (class "Default")
      (node (ref "C5") (pin "2") (pinfunction "2_2") (pintype "passive"))
      (node (ref "IC1") (pin "3") (pinfunction "C1-_3") (pintype "bidirectional"))
    )
    (net (code "29") (name "Net-(IC1A-C2+)") (class "Default")
      (node (ref "C6") (pin "1") (pinfunction "1_1") (pintype "passive"))
      (node (ref "IC1") (pin "4") (pinfunction "C2+_4") (pintype "bidirectional"))
    )
    (net (code "30") (name "Net-(IC1A-C2-)") (class "Default")
      (node (ref "C6") (pin "2") (pinfunction "2_2") (pintype "passive"))
      (node (ref "IC1") (pin "5") (pinfunction "C2-_5") (pintype "bidirectional"))
    )
    (net (code "31") (name "Net-(IC1A-R1IN)") (class "Default")
      (node (ref "IC1") (pin "13") (pinfunction "R1IN_13") (pintype "input"))
      (node (ref "X1") (pin "3") (pinfunction "F_3") (pintype "passive"))
    )
    (net (code "32") (name "Net-(IC1A-R2IN)") (class "Default")
      (node (ref "IC1") (pin "8") (pinfunction "R2IN_8") (pintype "input"))
      (node (ref "X1") (pin "7") (pinfunction "F_7") (pintype "passive"))
    )
    (net (code "33") (name "Net-(IC1A-T1OUT)") (class "Default")
      (node (ref "IC1") (pin "14") (pinfunction "T1OUT_14") (pintype "output"))
      (node (ref "X1") (pin "2") (pinfunction "F_2") (pintype "passive"))
    )
    (net (code "34") (name "Net-(IC1A-T2OUT)") (class "Default")
      (node (ref "IC1") (pin "7") (pinfunction "T2OUT_7") (pintype "output"))
      (node (ref "X1") (pin "8") (pinfunction "F_8") (pintype "passive"))
    )
    (net (code "35") (name "Net-(IC1A-V+)") (class "Default")
      (node (ref "C15") (pin "1") (pinfunction "1_1") (pintype "passive"))
      (node (ref "IC1") (pin "2") (pinfunction "V+_2") (pintype "bidirectional"))
    )
    (net (code "36") (name "Net-(IC1A-V-)") (class "Default")
      (node (ref "C16") (pin "2") (pinfunction "2_2") (pintype "passive"))
      (node (ref "IC1") (pin "6") (pinfunction "V-_6") (pintype "bidirectional"))
    )
    (net (code "37") (name "Net-(IC2-AREF)") (class "Default")
      (node (ref "C2") (pin "2") (pinfunction "2_2") (pintype "passive"))
      (node (ref "IC2") (pin "21") (pinfunction "AREF_21") (pintype "passive"))
    )
    (net (code "38") (name "Net-(IC2-PB0(ICP))") (class "Default")
      (node (ref "IC2") (pin "14") (pinfunction "PB0(ICP)_14") (pintype "bidirectional"))
      (node (ref "R8") (pin "2") (pinfunction "2_2") (pintype "passive"))
    )
    (net (code "39") (name "Net-(IC2-PB6(XTAL1{slash}TOSC1))") (class "Default")
      (node (ref "C8") (pin "2") (pinfunction "2_2") (pintype "passive"))
      (node (ref "IC2") (pin "9") (pinfunction "PB6(XTAL1/TOSC1)_9") (pintype "bidirectional"))
      (node (ref "Q1") (pin "2") (pinfunction "2_2") (pintype "passive"))
    )
    (net (code "40") (name "Net-(IC2-PB7(XTAL2{slash}TOSC2))") (class "Default")
      (node (ref "C9") (pin "2") (pinfunction "2_2") (pintype "passive"))
      (node (ref "IC2") (pin "10") (pinfunction "PB7(XTAL2/TOSC2)_10") (pintype "bidirectional"))
      (node (ref "Q1") (pin "1") (pinfunction "1_1") (pintype "passive"))
    )
    (net (code "41") (name "Net-(IC2-PC5(ADC5{slash}SCL))") (class "Default")
      (node (ref "IC2") (pin "28") (pinfunction "PC5(ADC5/SCL)_28") (pintype "bidirectional"))
      (node (ref "R18") (pin "1") (pinfunction "1_1") (pintype "passive"))
      (node (ref "R19") (pin "2") (pinfunction "2_2") (pintype "passive"))
    )
    (net (code "42") (name "Net-(IC2-PD5(T1))") (class "Default")
      (node (ref "IC2") (pin "11") (pinfunction "PD5(T1)_11") (pintype "bidirectional"))
      (node (ref "R11") (pin "2") (pinfunction "2_2") (pintype "passive"))
    )
    (net (code "43") (name "Net-(IC2-PD6(AIN0))") (class "Default")
      (node (ref "IC2") (pin "12") (pinfunction "PD6(AIN0)_12") (pintype "bidirectional"))
      (node (ref "R10") (pin "2") (pinfunction "2_2") (pintype "passive"))
    )
    (net (code "44") (name "Net-(IC2-PD7(AIN1))") (class "Default")
      (node (ref "IC2") (pin "13") (pinfunction "PD7(AIN1)_13") (pintype "bidirectional"))
      (node (ref "R9") (pin "2") (pinfunction "2_2") (pintype "passive"))
    )
    (net (code "45") (name "Net-(IC4-CII)") (class "Default")
      (node (ref "IC4") (pin "5") (pinfunction "CII_5") (pintype "bidirectional"))
      (node (ref "R14") (pin "2") (pinfunction "2_2") (pintype "passive"))
      (node (ref "R15") (pin "1") (pinfunction "1_1") (pintype "passive"))
    )
    (net (code "46") (name "Net-(IC4-DRC)") (class "Default")
      (node (ref "IC4") (pin "8") (pinfunction "DRC_8") (pintype "bidirectional"))
      (node (ref "R16") (pin "2") (pinfunction "2_2") (pintype "passive"))
    )
    (net (code "47") (name "Net-(IC4-IPK)") (class "Default")
      (node (ref "IC4") (pin "7") (pinfunction "IPK_7") (pintype "bidirectional"))
      (node (ref "L1") (pin "2") (pinfunction "2_2") (pintype "passive"))
      (node (ref "R16") (pin "1") (pinfunction "1_1") (pintype "passive"))
      (node (ref "R17") (pin "2") (pinfunction "2_2") (pintype "passive"))
    )
    (net (code "48") (name "Net-(IC4-SWC)") (class "Default")
      (node (ref "D2") (pin "A") (pinfunction "A_A") (pintype "passive"))
      (node (ref "IC4") (pin "1") (pinfunction "SWC_1") (pintype "bidirectional"))
      (node (ref "L1") (pin "1") (pinfunction "1_1") (pintype "passive"))
    )
    (net (code "49") (name "Net-(IC4-TC)") (class "Default")
      (node (ref "C18") (pin "1") (pinfunction "1_1") (pintype "passive"))
      (node (ref "IC4") (pin "3") (pinfunction "TC_3") (pintype "bidirectional"))
    )
    (net (code "50") (name "Net-(IC6A-QH*)") (class "Default")
      (node (ref "IC6") (pin "9") (pinfunction "QH*_9") (pintype "tri_state"))
      (node (ref "IC7") (pin "14") (pinfunction "SER_14") (pintype "input"))
      (node (ref "R37") (pin "2") (pinfunction "2_2") (pintype "passive"))
    )
    (net (code "51") (name "Net-(LED1-PadA)") (class "Default")
      (node (ref "LED1") (pin "A") (pinfunction "A_A") (pintype "passive"))
      (node (ref "R21") (pin "2") (pinfunction "2_2") (pintype "passive"))
    )
    (net (code "52") (name "Net-(LED2-PadA)") (class "Default")
      (node (ref "LED2") (pin "A") (pinfunction "A_A") (pintype "passive"))
      (node (ref "R22") (pin "2") (pinfunction "2_2") (pintype "passive"))
    )
    (net (code "53") (name "Net-(LED3-PadA)") (class "Default")
      (node (ref "LED3") (pin "A") (pinfunction "A_A") (pintype "passive"))
      (node (ref "R23") (pin "2") (pinfunction "2_2") (pintype "passive"))
    )
    (net (code "54") (name "Net-(LED4-PadA)") (class "Default")
      (node (ref "LED4") (pin "A") (pinfunction "A_A") (pintype "passive"))
      (node (ref "R24") (pin "2") (pinfunction "2_2") (pintype "passive"))
    )
    (net (code "55") (name "Net-(LED5-PadA)") (class "Default")
      (node (ref "LED5") (pin "A") (pinfunction "A_A") (pintype "passive"))
      (node (ref "R25") (pin "2") (pinfunction "2_2") (pintype "passive"))
    )
    (net (code "56") (name "Net-(LED6-PadA)") (class "Default")
      (node (ref "LED6") (pin "A") (pinfunction "A_A") (pintype "passive"))
      (node (ref "R26") (pin "2") (pinfunction "2_2") (pintype "passive"))
    )
    (net (code "57") (name "Net-(LED7-PadA)") (class "Default")
      (node (ref "LED7") (pin "A") (pinfunction "A_A") (pintype "passive"))
      (node (ref "R27") (pin "2") (pinfunction "2_2") (pintype "passive"))
    )
    (net (code "58") (name "Net-(LED8-PadA)") (class "Default")
      (node (ref "LED8") (pin "A") (pinfunction "A_A") (pintype "passive"))
      (node (ref "R28") (pin "2") (pinfunction "2_2") (pintype "passive"))
    )
    (net (code "59") (name "Net-(LED9-PadA)") (class "Default")
      (node (ref "LED9") (pin "A") (pinfunction "A_A") (pintype "passive"))
      (node (ref "R29") (pin "2") (pinfunction "2_2") (pintype "passive"))
    )
    (net (code "60") (name "Net-(LED10-PadA)") (class "Default")
      (node (ref "LED10") (pin "A") (pinfunction "A_A") (pintype "passive"))
      (node (ref "R30") (pin "2") (pinfunction "2_2") (pintype "passive"))
    )
    (net (code "61") (name "Net-(LED11-PadA)") (class "Default")
      (node (ref "LED11") (pin "A") (pinfunction "A_A") (pintype "passive"))
      (node (ref "R31") (pin "2") (pinfunction "2_2") (pintype "passive"))
    )
    (net (code "62") (name "Net-(LED12-PadA)") (class "Default")
      (node (ref "LED12") (pin "A") (pinfunction "A_A") (pintype "passive"))
      (node (ref "R32") (pin "2") (pinfunction "2_2") (pintype "passive"))
    )
    (net (code "63") (name "Net-(LED13-PadA)") (class "Default")
      (node (ref "LED13") (pin "A") (pinfunction "A_A") (pintype "passive"))
      (node (ref "R33") (pin "2") (pinfunction "2_2") (pintype "passive"))
    )
    (net (code "64") (name "Net-(LED14-PadA)") (class "Default")
      (node (ref "LED14") (pin "A") (pinfunction "A_A") (pintype "passive"))
      (node (ref "R34") (pin "2") (pinfunction "2_2") (pintype "passive"))
    )
    (net (code "65") (name "Net-(LED15-PadA)") (class "Default")
      (node (ref "LED15") (pin "A") (pinfunction "A_A") (pintype "passive"))
      (node (ref "R35") (pin "2") (pinfunction "2_2") (pintype "passive"))
    )
    (net (code "66") (name "Net-(LED16-PadA)") (class "Default")
      (node (ref "LED16") (pin "A") (pinfunction "A_A") (pintype "passive"))
      (node (ref "R36") (pin "2") (pinfunction "2_2") (pintype "passive"))
    )
    (net (code "67") (name "Net-(LED_G-PadA)") (class "Default")
      (node (ref "LED_G") (pin "A") (pinfunction "A_A") (pintype "passive"))
      (node (ref "R9") (pin "1") (pinfunction "1_1") (pintype "passive"))
    )
    (net (code "68") (name "Net-(LED_O-PadA)") (class "Default")
      (node (ref "LED_O") (pin "A") (pinfunction "A_A") (pintype "passive"))
      (node (ref "R11") (pin "1") (pinfunction "1_1") (pintype "passive"))
    )
    (net (code "69") (name "Net-(LED_R-PadA)") (class "Default")
      (node (ref "LED_R") (pin "A") (pinfunction "A_A") (pintype "passive"))
      (node (ref "R10") (pin "1") (pinfunction "1_1") (pintype "passive"))
    )
    (net (code "70") (name "Net-(LED_Y-PadA)") (class "Default")
      (node (ref "LED_Y") (pin "A") (pinfunction "A_A") (pintype "passive"))
      (node (ref "R8") (pin "1") (pinfunction "1_1") (pintype "passive"))
    )
    (net (code "71") (name "Net-(LSP1-PadMP)") (class "Default")
      (node (ref "LSP1") (pin "MP") (pinfunction "MP_MP") (pintype "passive"))
      (node (ref "Q2") (pin "D") (pinfunction "D_D") (pintype "passive"))
      (node (ref "R21") (pin "1") (pinfunction "1_1") (pintype "passive"))
    )
    (net (code "72") (name "Net-(LSP2-PadMP)") (class "Default")
      (node (ref "LSP2") (pin "MP") (pinfunction "MP_MP") (pintype "passive"))
      (node (ref "Q3") (pin "D") (pinfunction "D_D") (pintype "passive"))
      (node (ref "R22") (pin "1") (pinfunction "1_1") (pintype "passive"))
    )
    (net (code "73") (name "Net-(LSP3-PadMP)") (class "Default")
      (node (ref "LSP3") (pin "MP") (pinfunction "MP_MP") (pintype "passive"))
      (node (ref "Q4") (pin "D") (pinfunction "D_D") (pintype "passive"))
      (node (ref "R23") (pin "1") (pinfunction "1_1") (pintype "passive"))
    )
    (net (code "74") (name "Net-(LSP4-PadMP)") (class "Default")
      (node (ref "LSP4") (pin "MP") (pinfunction "MP_MP") (pintype "passive"))
      (node (ref "Q5") (pin "D") (pinfunction "D_D") (pintype "passive"))
      (node (ref "R24") (pin "1") (pinfunction "1_1") (pintype "passive"))
    )
    (net (code "75") (name "Net-(LSP5-PadMP)") (class "Default")
      (node (ref "LSP5") (pin "MP") (pinfunction "MP_MP") (pintype "passive"))
      (node (ref "Q6") (pin "D") (pinfunction "D_D") (pintype "passive"))
      (node (ref "R25") (pin "1") (pinfunction "1_1") (pintype "passive"))
    )
    (net (code "76") (name "Net-(LSP6-PadMP)") (class "Default")
      (node (ref "LSP6") (pin "MP") (pinfunction "MP_MP") (pintype "passive"))
      (node (ref "Q7") (pin "D") (pinfunction "D_D") (pintype "passive"))
      (node (ref "R26") (pin "1") (pinfunction "1_1") (pintype "passive"))
    )
    (net (code "77") (name "Net-(LSP7-PadMP)") (class "Default")
      (node (ref "LSP7") (pin "MP") (pinfunction "MP_MP") (pintype "passive"))
      (node (ref "Q8") (pin "D") (pinfunction "D_D") (pintype "passive"))
      (node (ref "R27") (pin "1") (pinfunction "1_1") (pintype "passive"))
    )
    (net (code "78") (name "Net-(LSP8-PadMP)") (class "Default")
      (node (ref "LSP8") (pin "MP") (pinfunction "MP_MP") (pintype "passive"))
      (node (ref "Q9") (pin "D") (pinfunction "D_D") (pintype "passive"))
      (node (ref "R28") (pin "1") (pinfunction "1_1") (pintype "passive"))
    )
    (net (code "79") (name "Net-(LSP9-PadMP)") (class "Default")
      (node (ref "LSP9") (pin "MP") (pinfunction "MP_MP") (pintype "passive"))
      (node (ref "Q10") (pin "D") (pinfunction "D_D") (pintype "passive"))
      (node (ref "R29") (pin "1") (pinfunction "1_1") (pintype "passive"))
    )
    (net (code "80") (name "Net-(LSP10-PadMP)") (class "Default")
      (node (ref "LSP10") (pin "MP") (pinfunction "MP_MP") (pintype "passive"))
      (node (ref "Q11") (pin "D") (pinfunction "D_D") (pintype "passive"))
      (node (ref "R30") (pin "1") (pinfunction "1_1") (pintype "passive"))
    )
    (net (code "81") (name "Net-(LSP11-PadMP)") (class "Default")
      (node (ref "LSP11") (pin "MP") (pinfunction "MP_MP") (pintype "passive"))
      (node (ref "Q12") (pin "D") (pinfunction "D_D") (pintype "passive"))
      (node (ref "R31") (pin "1") (pinfunction "1_1") (pintype "passive"))
    )
    (net (code "82") (name "Net-(LSP12-PadMP)") (class "Default")
      (node (ref "LSP12") (pin "MP") (pinfunction "MP_MP") (pintype "passive"))
      (node (ref "Q13") (pin "D") (pinfunction "D_D") (pintype "passive"))
      (node (ref "R32") (pin "1") (pinfunction "1_1") (pintype "passive"))
    )
    (net (code "83") (name "Net-(LSP13-PadMP)") (class "Default")
      (node (ref "LSP13") (pin "MP") (pinfunction "MP_MP") (pintype "passive"))
      (node (ref "Q14") (pin "D") (pinfunction "D_D") (pintype "passive"))
      (node (ref "R33") (pin "1") (pinfunction "1_1") (pintype "passive"))
    )
    (net (code "84") (name "Net-(LSP14-PadMP)") (class "Default")
      (node (ref "LSP14") (pin "MP") (pinfunction "MP_MP") (pintype "passive"))
      (node (ref "Q15") (pin "D") (pinfunction "D_D") (pintype "passive"))
      (node (ref "R34") (pin "1") (pinfunction "1_1") (pintype "passive"))
    )
    (net (code "85") (name "Net-(LSP15-PadMP)") (class "Default")
      (node (ref "LSP15") (pin "MP") (pinfunction "MP_MP") (pintype "passive"))
      (node (ref "Q16") (pin "D") (pinfunction "D_D") (pintype "passive"))
      (node (ref "R35") (pin "1") (pinfunction "1_1") (pintype "passive"))
    )
    (net (code "86") (name "Net-(LSP16-PadMP)") (class "Default")
      (node (ref "LSP16") (pin "MP") (pinfunction "MP_MP") (pintype "passive"))
      (node (ref "Q17") (pin "D") (pinfunction "D_D") (pintype "passive"))
      (node (ref "R36") (pin "1") (pinfunction "1_1") (pintype "passive"))
    )
    (net (code "87") (name "Net-(LSP_1_5_9_13-PadMP)") (class "Default")
      (node (ref "LSP_1_5_9_13") (pin "MP") (pinfunction "MP_MP") (pintype "passive"))
      (node (ref "LSP_2_6_10_14") (pin "MP") (pinfunction "MP_MP") (pintype "passive"))
      (node (ref "LSP_3_7_11_15") (pin "MP") (pinfunction "MP_MP") (pintype "passive"))
      (node (ref "LSP_4_8_12_16") (pin "MP") (pinfunction "MP_MP") (pintype "passive"))
      (node (ref "R_Z") (pin "1") (pinfunction "1_1") (pintype "passive"))
    )
    (net (code "88") (name "Net-(R2-Pad2)") (class "Default")
      (node (ref "R2") (pin "2") (pinfunction "2_2") (pintype "passive"))
      (node (ref "U$4") (pin "DIO2") (pinfunction "DIO2_DIO2") (pintype "bidirectional"))
    )
    (net (code "89") (name "Net-(R3-Pad1)") (class "Default")
      (node (ref "R3") (pin "1") (pinfunction "1_1") (pintype "passive"))
      (node (ref "U$4") (pin "NRES") (pinfunction "NRES_NRES") (pintype "bidirectional"))
    )
    (net (code "90") (name "Net-(R4-Pad2)") (class "Default")
      (node (ref "R4") (pin "2") (pinfunction "2_2") (pintype "passive"))
      (node (ref "U$4") (pin "SCK") (pinfunction "SCK_SCK") (pintype "input"))
    )
    (net (code "91") (name "Net-(R5-Pad2)") (class "Default")
      (node (ref "R5") (pin "2") (pinfunction "2_2") (pintype "passive"))
      (node (ref "U$4") (pin "SDO") (pinfunction "SDO_SDO") (pintype "output"))
    )
    (net (code "92") (name "Net-(R6-Pad2)") (class "Default")
      (node (ref "R6") (pin "2") (pinfunction "2_2") (pintype "passive"))
      (node (ref "U$4") (pin "SDI") (pinfunction "SDI_SDI") (pintype "input"))
    )
    (net (code "93") (name "RTS") (class "Default")
      (node (ref "IC1") (pin "10") (pinfunction "T2IN_10") (pintype "input"))
      (node (ref "IC2") (pin "4") (pinfunction "PD2(INT0)_4") (pintype "bidirectional"))
    )
    (net (code "94") (name "RX") (class "Default")
      (node (ref "IC1") (pin "12") (pinfunction "R1OUT_12") (pintype "output"))
      (node (ref "IC2") (pin "2") (pinfunction "PD0(RXD)_2") (pintype "bidirectional"))
    )
    (net (code "95") (name "SCK") (class "Default")
      (node (ref "IC2") (pin "19") (pinfunction "PB5(SCK)_19") (pintype "bidirectional"))
      (node (ref "R4") (pin "1") (pinfunction "1_1") (pintype "passive"))
      (node (ref "SV2") (pin "7") (pinfunction "7_7") (pintype "passive"))
    )
    (net (code "96") (name "SHIFT_OE") (class "Default")
      (node (ref "IC2") (pin "24") (pinfunction "PC1(ADC1)_24") (pintype "bidirectional"))
      (node (ref "IC6") (pin "13") (pinfunction "G_13") (pintype "input"))
      (node (ref "IC7") (pin "13") (pinfunction "G_13") (pintype "input"))
      (node (ref "R12") (pin "1") (pinfunction "1_1") (pintype "passive"))
    )
    (net (code "97") (name "SHIFT_RCK") (class "Default")
      (node (ref "IC2") (pin "25") (pinfunction "PC2(ADC2)_25") (pintype "bidirectional"))
      (node (ref "IC6") (pin "12") (pinfunction "RCK_12") (pintype "input"))
      (node (ref "IC7") (pin "12") (pinfunction "RCK_12") (pintype "input"))
    )
    (net (code "98") (name "SHIFT_SCK") (class "Default")
      (node (ref "IC2") (pin "26") (pinfunction "PC3(ADC3)_26") (pintype "bidirectional"))
      (node (ref "IC6") (pin "11") (pinfunction "SCK_11") (pintype "input"))
      (node (ref "IC7") (pin "11") (pinfunction "SCK_11") (pintype "input"))
    )
    (net (code "99") (name "SHIFT_SER") (class "Default")
      (node (ref "IC2") (pin "23") (pinfunction "PC0(ADC0)_23") (pintype "bidirectional"))
      (node (ref "IC6") (pin "14") (pinfunction "SER_14") (pintype "input"))
      (node (ref "R20") (pin "1") (pinfunction "1_1") (pintype "passive"))
    )
    (net (code "100") (name "TX") (class "Default")
      (node (ref "IC1") (pin "11") (pinfunction "T1IN_11") (pintype "input"))
      (node (ref "IC2") (pin "3") (pinfunction "PD1(TXD)_3") (pintype "bidirectional"))
    )
    (net (code "101") (name "V_BATT") (class "Default")
      (node (ref "C13") (pin "+") (pinfunction "+_+") (pintype "passive"))
      (node (ref "C19") (pin "+") (pinfunction "+_+") (pintype "passive"))
      (node (ref "C20") (pin "1") (pinfunction "1_1") (pintype "passive"))
      (node (ref "C25") (pin "1") (pinfunction "1_1") (pintype "passive"))
      (node (ref "D3") (pin "C") (pinfunction "C_C") (pintype "passive"))
      (node (ref "IC4") (pin "6") (pinfunction "VCC_6") (pintype "bidirectional"))
      (node (ref "IC8") (pin "3") (pinfunction "IN_3") (pintype "input"))
      (node (ref "PWR_SW2") (pin "MP") (pinfunction "MP_MP") (pintype "passive"))
      (node (ref "R17") (pin "1") (pinfunction "1_1") (pintype "passive"))
      (node (ref "R18") (pin "2") (pinfunction "2_2") (pintype "passive"))
      (node (ref "U$3") (pin "VIN") (pinfunction "VIN_VIN") (pintype "bidirectional"))
    )
    (net (code "102") (name "unconnected-(IC2-PD4(XCK{slash}T0)-Pad6)") (class "Default")
      (node (ref "IC2") (pin "6") (pinfunction "PD4(XCK/T0)_6") (pintype "bidirectional"))
    )
    (net (code "103") (name "unconnected-(IC7A-QH*-Pad9)") (class "Default")
      (node (ref "IC7") (pin "9") (pinfunction "QH*_9") (pintype "tri_state"))
    )
    (net (code "104") (name "unconnected-(SV2-Pad3)") (class "Default")
      (node (ref "SV2") (pin "3") (pinfunction "3_3") (pintype "passive"))
    )
    (net (code "105") (name "unconnected-(U$4-PadANT)") (class "Default")
      (node (ref "U$4") (pin "ANT") (pinfunction "ANT_ANT") (pintype "bidirectional"))
    )
    (net (code "106") (name "unconnected-(U$4-PadDIO0)") (class "Default")
      (node (ref "U$4") (pin "DIO0") (pinfunction "DIO0_DIO0") (pintype "bidirectional"))
    )
    (net (code "107") (name "unconnected-(U$4-PadDIO1)") (class "Default")
      (node (ref "U$4") (pin "DIO1") (pinfunction "DIO1_DIO1") (pintype "bidirectional"))
    )
    (net (code "108") (name "unconnected-(U$4-PadDIO3)") (class "Default")
      (node (ref "U$4") (pin "DIO3") (pinfunction "DIO3_DIO3") (pintype "bidirectional"))
    )
    (net (code "109") (name "unconnected-(U$4-PadDIO5)") (class "Default")
      (node (ref "U$4") (pin "DIO5") (pinfunction "DIO5_DIO5") (pintype "bidirectional"))
    )
    (net (code "110") (name "{slash}RST") (class "Default")
      (node (ref "C7") (pin "1") (pinfunction "1_1") (pintype "passive"))
      (node (ref "IC2") (pin "1") (pinfunction "PC6(/RESET)_1") (pintype "bidirectional"))
      (node (ref "R1") (pin "1") (pinfunction "1_1") (pintype "passive"))
      (node (ref "SV2") (pin "5") (pinfunction "5_5") (pintype "passive"))
    )
  )
)
